# FT232R-Breakout-v36-0805.net
KiCad netlist of a schematic drawn in EAGLE
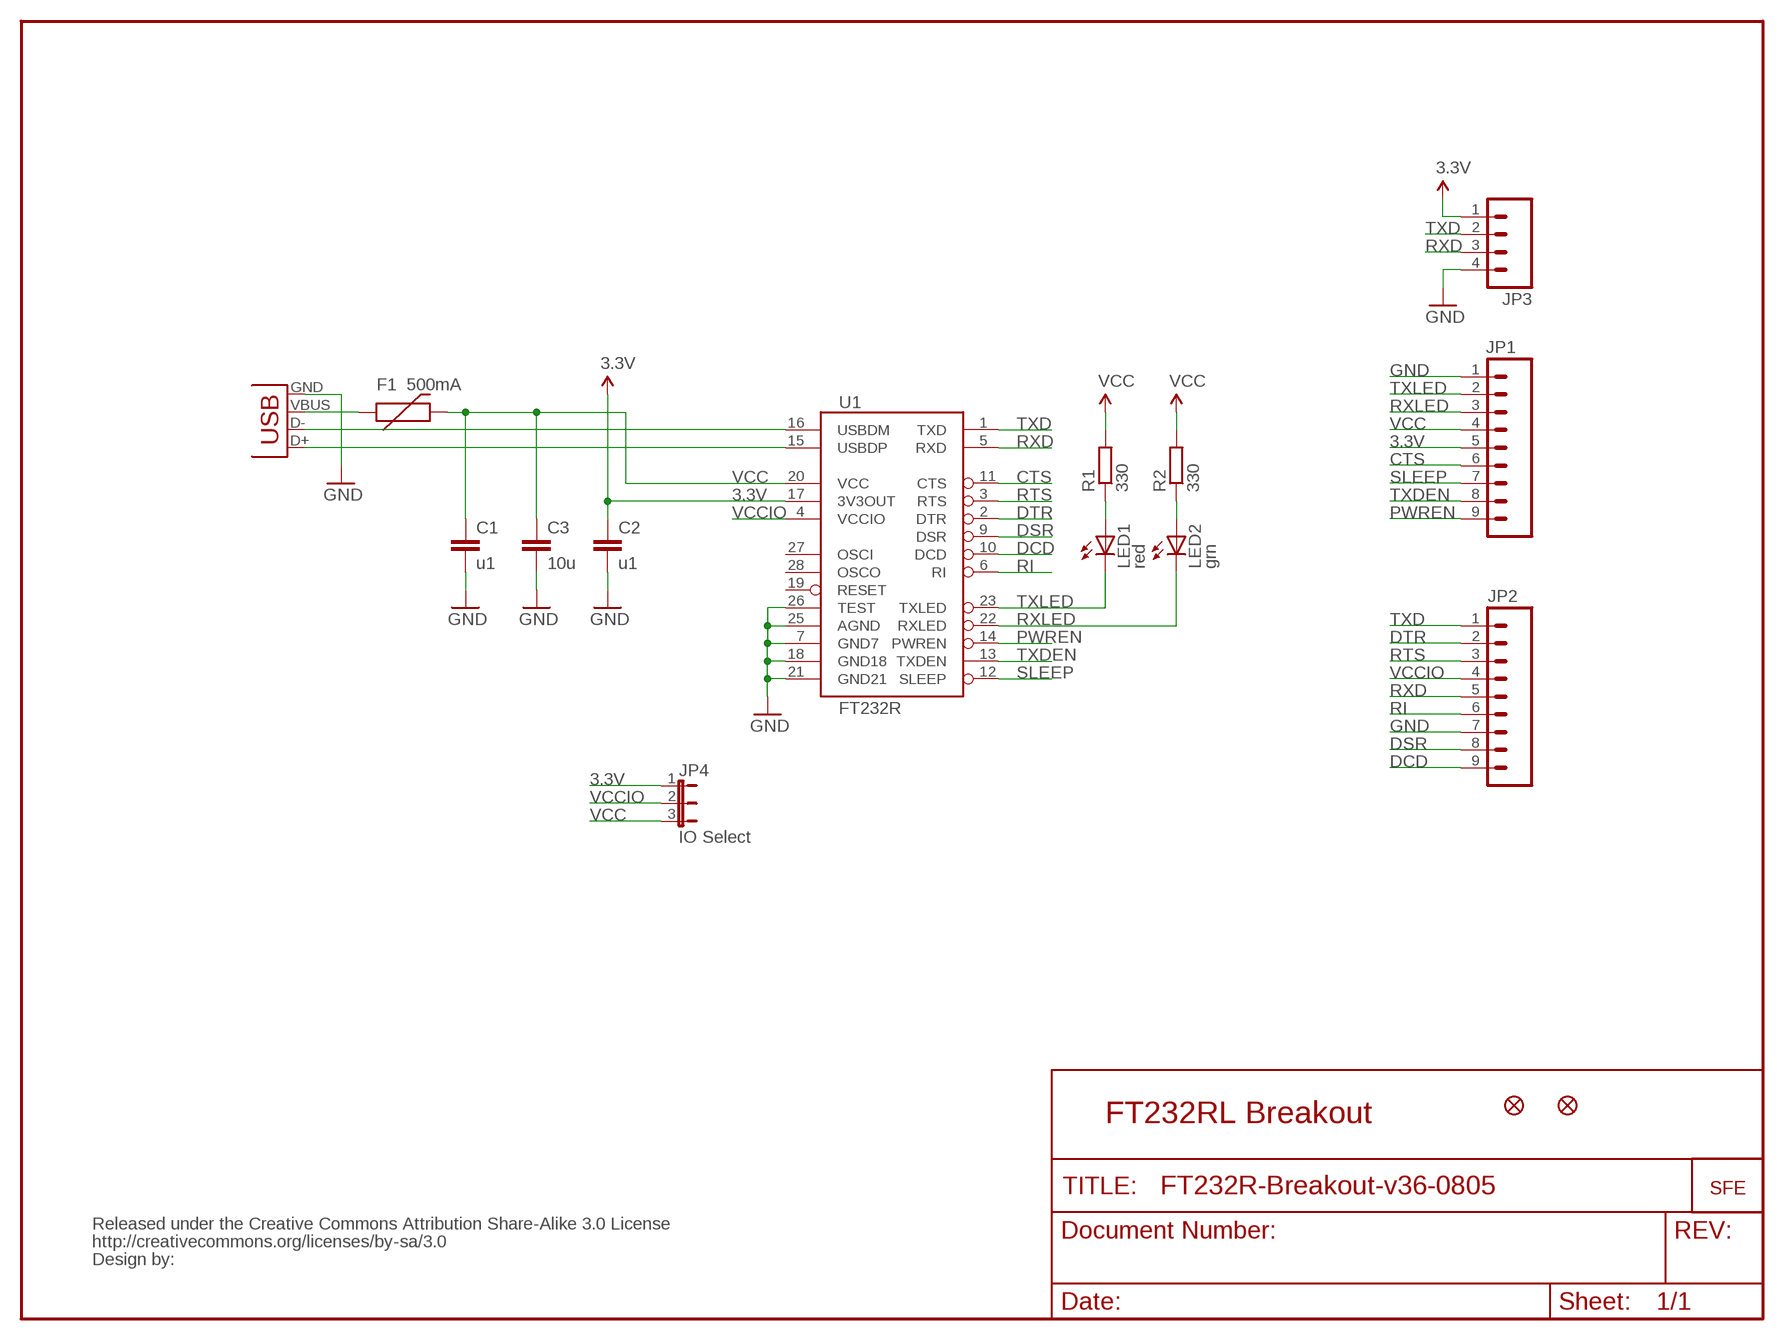
[diagram p0: schematic, sheet 1]

(export (version "E")
  (design (tool "Eeschema 10.0.6"))
  (components
    (comp (ref "C1")
      (value "u1")
      (footprint "eagle-import:C0805K")
      (libsource (lib "eagle-import") (part "C-EUC0805K"))
    )
    (comp (ref "C2")
      (value "u1")
      (footprint "eagle-import:C0805K")
      (libsource (lib "eagle-import") (part "C-EUC0805K"))
    )
    (comp (ref "C3")
      (value "10u")
      (footprint "eagle-import:C0805K")
      (libsource (lib "eagle-import") (part "C-EUC0805K"))
    )
    (comp (ref "F1")
      (value "500mA")
      (footprint "eagle-import:0603")
      (libsource (lib "eagle-import") (part "PTC0603"))
    )
    (comp (ref "JP1")
      (value "M09")
      (footprint "eagle-import:1X09")
      (libsource (lib "eagle-import") (part "M09"))
    )
    (comp (ref "JP2")
      (value "M09")
      (footprint "eagle-import:1X09")
      (libsource (lib "eagle-import") (part "M09"))
    )
    (comp (ref "JP3")
      (value "M04PTH")
      (footprint "eagle-import:1X04")
      (libsource (lib "eagle-import") (part "M04PTH"))
    )
    (comp (ref "JP4")
      (value "IO Select")
      (footprint "eagle-import:SJ_3")
      (libsource (lib "eagle-import") (part "JUMPER-3SMD"))
    )
    (comp (ref "JP5")
      (value "FIDUCIAL1X2")
      (footprint "eagle-import:FIDUCIAL-1X2")
      (libsource (lib "eagle-import") (part "FIDUCIAL1X2"))
    )
    (comp (ref "JP6")
      (value "FIDUCIAL1X2")
      (footprint "eagle-import:FIDUCIAL-1X2")
      (libsource (lib "eagle-import") (part "FIDUCIAL1X2"))
    )
    (comp (ref "LED1")
      (value "red")
      (footprint "eagle-import:CHIP-LED0805")
      (libsource (lib "eagle-import") (part "LEDCHIP-LED0805"))
    )
    (comp (ref "LED2")
      (value "grn")
      (footprint "eagle-import:CHIP-LED0805")
      (libsource (lib "eagle-import") (part "LEDCHIP-LED0805"))
    )
    (comp (ref "R1")
      (value "330")
      (footprint "eagle-import:M0805")
      (libsource (lib "eagle-import") (part "R-EU_M0805"))
    )
    (comp (ref "R2")
      (value "330")
      (footprint "eagle-import:M0805")
      (libsource (lib "eagle-import") (part "R-EU_M0805"))
    )
    (comp (ref "U$1")
      (value "CREATIVE_COMMONS")
      (footprint "eagle-import:CREATIVE_COMMONS")
      (libsource (lib "eagle-import") (part "CREATIVE_COMMONS"))
    )
    (comp (ref "U$2")
      (value "LOGO-SFENEW")
      (footprint "eagle-import:SFE-NEW-WEBLOGO")
      (libsource (lib "eagle-import") (part "LOGO-SFENEW"))
    )
    (comp (ref "U1")
      (value "FT232R")
      (footprint "eagle-import:SSOP28DB")
      (libsource (lib "eagle-import") (part "FT232RLSSOP"))
    )
    (comp (ref "X2")
      (value "USBSMD")
      (footprint "eagle-import:USB-MINIB")
      (libsource (lib "eagle-import") (part "USBSMD"))
    )
  )
  (nets
    (net (code "1") (name "/CTS") (class "Default")
      (node (ref "JP1") (pin "6") (pinfunction "6_6") (pintype "passive"))
      (node (ref "U1") (pin "11") (pinfunction "CTS_11") (pintype "input"))
    )
    (net (code "2") (name "/DCD") (class "Default")
      (node (ref "JP2") (pin "9") (pinfunction "9_9") (pintype "passive"))
      (node (ref "U1") (pin "10") (pinfunction "DCD_10") (pintype "input"))
    )
    (net (code "3") (name "/DSR") (class "Default")
      (node (ref "JP2") (pin "8") (pinfunction "8_8") (pintype "passive"))
      (node (ref "U1") (pin "9") (pinfunction "DSR_9") (pintype "input"))
    )
    (net (code "4") (name "/DTR") (class "Default")
      (node (ref "JP2") (pin "2") (pinfunction "2_2") (pintype "passive"))
      (node (ref "U1") (pin "2") (pinfunction "DTR_2") (pintype "output"))
    )
    (net (code "5") (name "/PWREN") (class "Default")
      (node (ref "JP1") (pin "9") (pinfunction "9_9") (pintype "passive"))
      (node (ref "U1") (pin "14") (pinfunction "PWREN_14") (pintype "input"))
    )
    (net (code "6") (name "/RI") (class "Default")
      (node (ref "JP2") (pin "6") (pinfunction "6_6") (pintype "passive"))
      (node (ref "U1") (pin "6") (pinfunction "RI_6") (pintype "input"))
    )
    (net (code "7") (name "/RTS") (class "Default")
      (node (ref "JP2") (pin "3") (pinfunction "3_3") (pintype "passive"))
      (node (ref "U1") (pin "3") (pinfunction "RTS_3") (pintype "output"))
    )
    (net (code "8") (name "/RXD") (class "Default")
      (node (ref "JP2") (pin "5") (pinfunction "5_5") (pintype "passive"))
      (node (ref "JP3") (pin "3") (pinfunction "3_3") (pintype "passive"))
      (node (ref "U1") (pin "5") (pinfunction "RXD_5") (pintype "input"))
    )
    (net (code "9") (name "/RXLED") (class "Default")
      (node (ref "JP1") (pin "3") (pinfunction "3_3") (pintype "passive"))
      (node (ref "LED2") (pin "C") (pinfunction "C_C") (pintype "passive"))
      (node (ref "U1") (pin "22") (pinfunction "RXLED_22") (pintype "input"))
    )
    (net (code "10") (name "/SLEEP") (class "Default")
      (node (ref "JP1") (pin "7") (pinfunction "7_7") (pintype "passive"))
      (node (ref "U1") (pin "12") (pinfunction "SLEEP_12") (pintype "input"))
    )
    (net (code "11") (name "/TXD") (class "Default")
      (node (ref "JP2") (pin "1") (pinfunction "1_1") (pintype "passive"))
      (node (ref "JP3") (pin "2") (pinfunction "2_2") (pintype "passive"))
      (node (ref "U1") (pin "1") (pinfunction "TXD_1") (pintype "output"))
    )
    (net (code "12") (name "/TXDEN") (class "Default")
      (node (ref "JP1") (pin "8") (pinfunction "8_8") (pintype "passive"))
      (node (ref "U1") (pin "13") (pinfunction "TXDEN_13") (pintype "input"))
    )
    (net (code "13") (name "/TXLED") (class "Default")
      (node (ref "JP1") (pin "2") (pinfunction "2_2") (pintype "passive"))
      (node (ref "LED1") (pin "C") (pinfunction "C_C") (pintype "passive"))
      (node (ref "U1") (pin "23") (pinfunction "TXLED_23") (pintype "input"))
    )
    (net (code "14") (name "/VCCIO") (class "Default")
      (node (ref "JP2") (pin "4") (pinfunction "4_4") (pintype "passive"))
      (node (ref "JP4") (pin "2") (pinfunction "2_2") (pintype "passive"))
      (node (ref "U1") (pin "4") (pinfunction "VCCIO_4") (pintype "power_in"))
    )
    (net (code "15") (name "3.3V") (class "Default")
      (node (ref "C2") (pin "1") (pinfunction "1_1") (pintype "passive"))
      (node (ref "JP1") (pin "5") (pinfunction "5_5") (pintype "passive"))
      (node (ref "JP3") (pin "1") (pinfunction "1_1") (pintype "passive"))
      (node (ref "JP4") (pin "1") (pinfunction "1_1") (pintype "passive"))
      (node (ref "U1") (pin "17") (pinfunction "3V3OUT_17") (pintype "output"))
    )
    (net (code "16") (name "GND") (class "Default")
      (node (ref "C1") (pin "2") (pinfunction "2_2") (pintype "passive"))
      (node (ref "C2") (pin "2") (pinfunction "2_2") (pintype "passive"))
      (node (ref "C3") (pin "2") (pinfunction "2_2") (pintype "passive"))
      (node (ref "JP1") (pin "1") (pinfunction "1_1") (pintype "passive"))
      (node (ref "JP2") (pin "7") (pinfunction "7_7") (pintype "passive"))
      (node (ref "JP3") (pin "4") (pinfunction "4_4") (pintype "passive"))
      (node (ref "U1") (pin "18") (pinfunction "GND18_18") (pintype "power_in"))
      (node (ref "U1") (pin "21") (pinfunction "GND21_21") (pintype "power_in"))
      (node (ref "U1") (pin "25") (pinfunction "AGND_25") (pintype "power_in"))
      (node (ref "U1") (pin "26") (pinfunction "TEST_26") (pintype "input"))
      (node (ref "U1") (pin "7") (pinfunction "GND7_7") (pintype "power_in"))
      (node (ref "X2") (pin "GND") (pinfunction "GND_GND") (pintype "bidirectional"))
    )
    (net (code "17") (name "Net-(F1-Pad1)") (class "Default")
      (node (ref "F1") (pin "1") (pinfunction "1_1") (pintype "bidirectional"))
      (node (ref "X2") (pin "VBUS") (pinfunction "VBUS_VBUS") (pintype "bidirectional"))
    )
    (net (code "18") (name "Net-(LED1-PadA)") (class "Default")
      (node (ref "LED1") (pin "A") (pinfunction "A_A") (pintype "passive"))
      (node (ref "R1") (pin "1") (pinfunction "1_1") (pintype "passive"))
    )
    (net (code "19") (name "Net-(LED2-PadA)") (class "Default")
      (node (ref "LED2") (pin "A") (pinfunction "A_A") (pintype "passive"))
      (node (ref "R2") (pin "1") (pinfunction "1_1") (pintype "passive"))
    )
    (net (code "20") (name "Net-(U1-USBDM)") (class "Default")
      (node (ref "U1") (pin "16") (pinfunction "USBDM_16") (pintype "bidirectional"))
      (node (ref "X2") (pin "D-") (pinfunction "D-_D-") (pintype "bidirectional"))
    )
    (net (code "21") (name "Net-(U1-USBDP)") (class "Default")
      (node (ref "U1") (pin "15") (pinfunction "USBDP_15") (pintype "bidirectional"))
      (node (ref "X2") (pin "D+") (pinfunction "D+_D+") (pintype "bidirectional"))
    )
    (net (code "22") (name "VCC") (class "Default")
      (node (ref "C1") (pin "1") (pinfunction "1_1") (pintype "passive"))
      (node (ref "C3") (pin "1") (pinfunction "1_1") (pintype "passive"))
      (node (ref "F1") (pin "2") (pinfunction "2_2") (pintype "bidirectional"))
      (node (ref "JP1") (pin "4") (pinfunction "4_4") (pintype "passive"))
      (node (ref "JP4") (pin "3") (pinfunction "3_3") (pintype "passive"))
      (node (ref "R1") (pin "2") (pinfunction "2_2") (pintype "passive"))
      (node (ref "R2") (pin "2") (pinfunction "2_2") (pintype "passive"))
      (node (ref "U1") (pin "20") (pinfunction "VCC_20") (pintype "power_in"))
    )
    (net (code "23") (name "unconnected-(U1-OSCI-Pad27)") (class "Default")
      (node (ref "U1") (pin "27") (pinfunction "OSCI_27") (pintype "input"))
    )
    (net (code "24") (name "unconnected-(U1-OSCO-Pad28)") (class "Default")
      (node (ref "U1") (pin "28") (pinfunction "OSCO_28") (pintype "output"))
    )
    (net (code "25") (name "unconnected-(U1-RESET-Pad19)") (class "Default")
      (node (ref "U1") (pin "19") (pinfunction "RESET_19") (pintype "input"))
    )
  )
)
